# 5_-CONNECTORS.net
KiCad netlist of a schematic drawn in Altium Designer
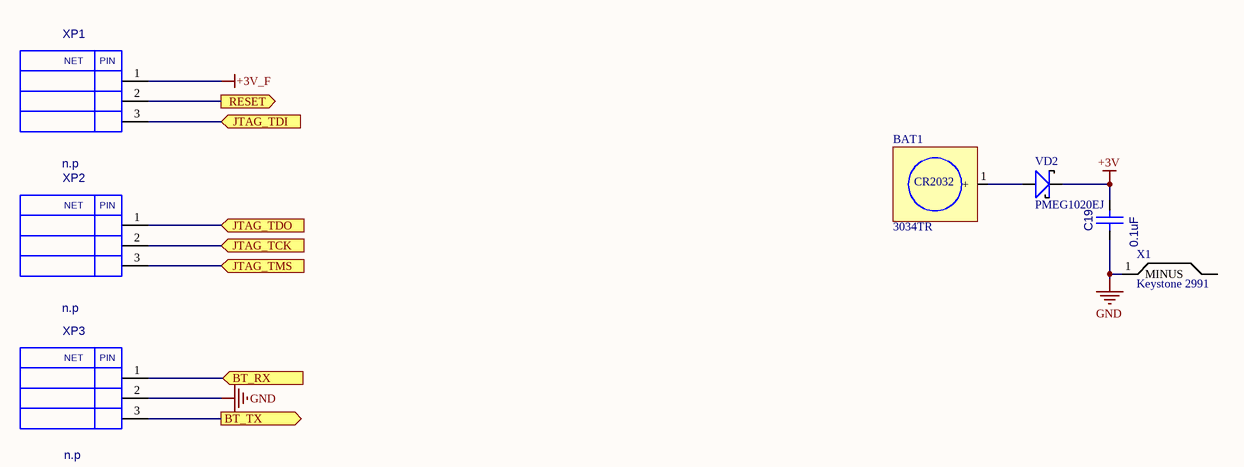
[diagram p0: [5]-CONNECTORS.SchDoc]

(export (version "E")
  (design (tool "Eeschema 10.0.6"))
  (components
    (comp (ref "BAT1")
      (value "3034TR")
      (footprint "3034-TR")
      (description "CR2032 holder smd")
      (libsource (lib "fizik_lib") (part "3034"))
    )
    (comp (ref "C19")
      (value "0.1uF")
      (footprint "CC0603")
      (description "CC0603")
      (libsource (lib "fizik_lib") (part "CC0603"))
    )
    (comp (ref "VD2")
      (value "PMEG1020EJ")
      (footprint "SOD323")
      (libsource (lib "fizik_lib") (part "PMEG2010"))
    )
    (comp (ref "X1")
      (value "Keystone 2991")
      (footprint "Keystone_2991")
      (description "Keystone minus pin for CR2032")
      (libsource (lib "fizik_lib") (part "Keystone 2991"))
    )
    (comp (ref "XP1")
      (value "n.p")
      (footprint "PLS-03")
      (description "PLS03")
      (libsource (lib "fizik_lib") (part "PLS03"))
    )
    (comp (ref "XP2")
      (value "n.p")
      (footprint "PLS-03")
      (description "PLS03")
      (libsource (lib "fizik_lib") (part "PLS03"))
    )
    (comp (ref "XP3")
      (value "n.p")
      (footprint "PLS-03")
      (description "PLS03")
      (libsource (lib "fizik_lib") (part "PLS03"))
    )
  )
  (nets
    (net (code "1") (name "+3V") (class "Default")
      (node (ref "C19") (pin "2") (pinfunction "B_2") (pintype "passive"))
      (node (ref "VD2") (pin "2") (pinfunction "K_2") (pintype "passive"))
    )
    (net (code "2") (name "+3V_F") (class "Default")
      (node (ref "XP1") (pin "1") (pinfunction "1_1") (pintype "passive"))
    )
    (net (code "3") (name "/BT_RX") (class "Default")
      (node (ref "XP3") (pin "1") (pinfunction "1_1") (pintype "passive"))
    )
    (net (code "4") (name "/BT_TX") (class "Default")
      (node (ref "XP3") (pin "3") (pinfunction "3_3") (pintype "passive"))
    )
    (net (code "5") (name "/JTAG_TCK") (class "Default")
      (node (ref "XP2") (pin "2") (pinfunction "2_2") (pintype "passive"))
    )
    (net (code "6") (name "/JTAG_TDI") (class "Default")
      (node (ref "XP1") (pin "3") (pinfunction "3_3") (pintype "passive"))
    )
    (net (code "7") (name "/JTAG_TDO") (class "Default")
      (node (ref "XP2") (pin "1") (pinfunction "1_1") (pintype "passive"))
    )
    (net (code "8") (name "/JTAG_TMS") (class "Default")
      (node (ref "XP2") (pin "3") (pinfunction "3_3") (pintype "passive"))
    )
    (net (code "9") (name "/RESET") (class "Default")
      (node (ref "XP1") (pin "2") (pinfunction "2_2") (pintype "passive"))
    )
    (net (code "10") (name "GND") (class "Default")
      (node (ref "C19") (pin "1") (pinfunction "A_1") (pintype "passive"))
      (node (ref "X1") (pin "1") (pinfunction "MINUS_1") (pintype "passive"))
      (node (ref "XP3") (pin "2") (pinfunction "2_2") (pintype "passive"))
    )
    (net (code "11") (name "Net-(BAT1-+)") (class "Default")
      (node (ref "BAT1") (pin "1") (pinfunction "+_1") (pintype "passive"))
      (node (ref "VD2") (pin "1") (pinfunction "A_1") (pintype "passive"))
    )
  )
)
